# SCH_ART-BadgeV2_0.net
KiCad netlist of a schematic drawn in EasyEDA
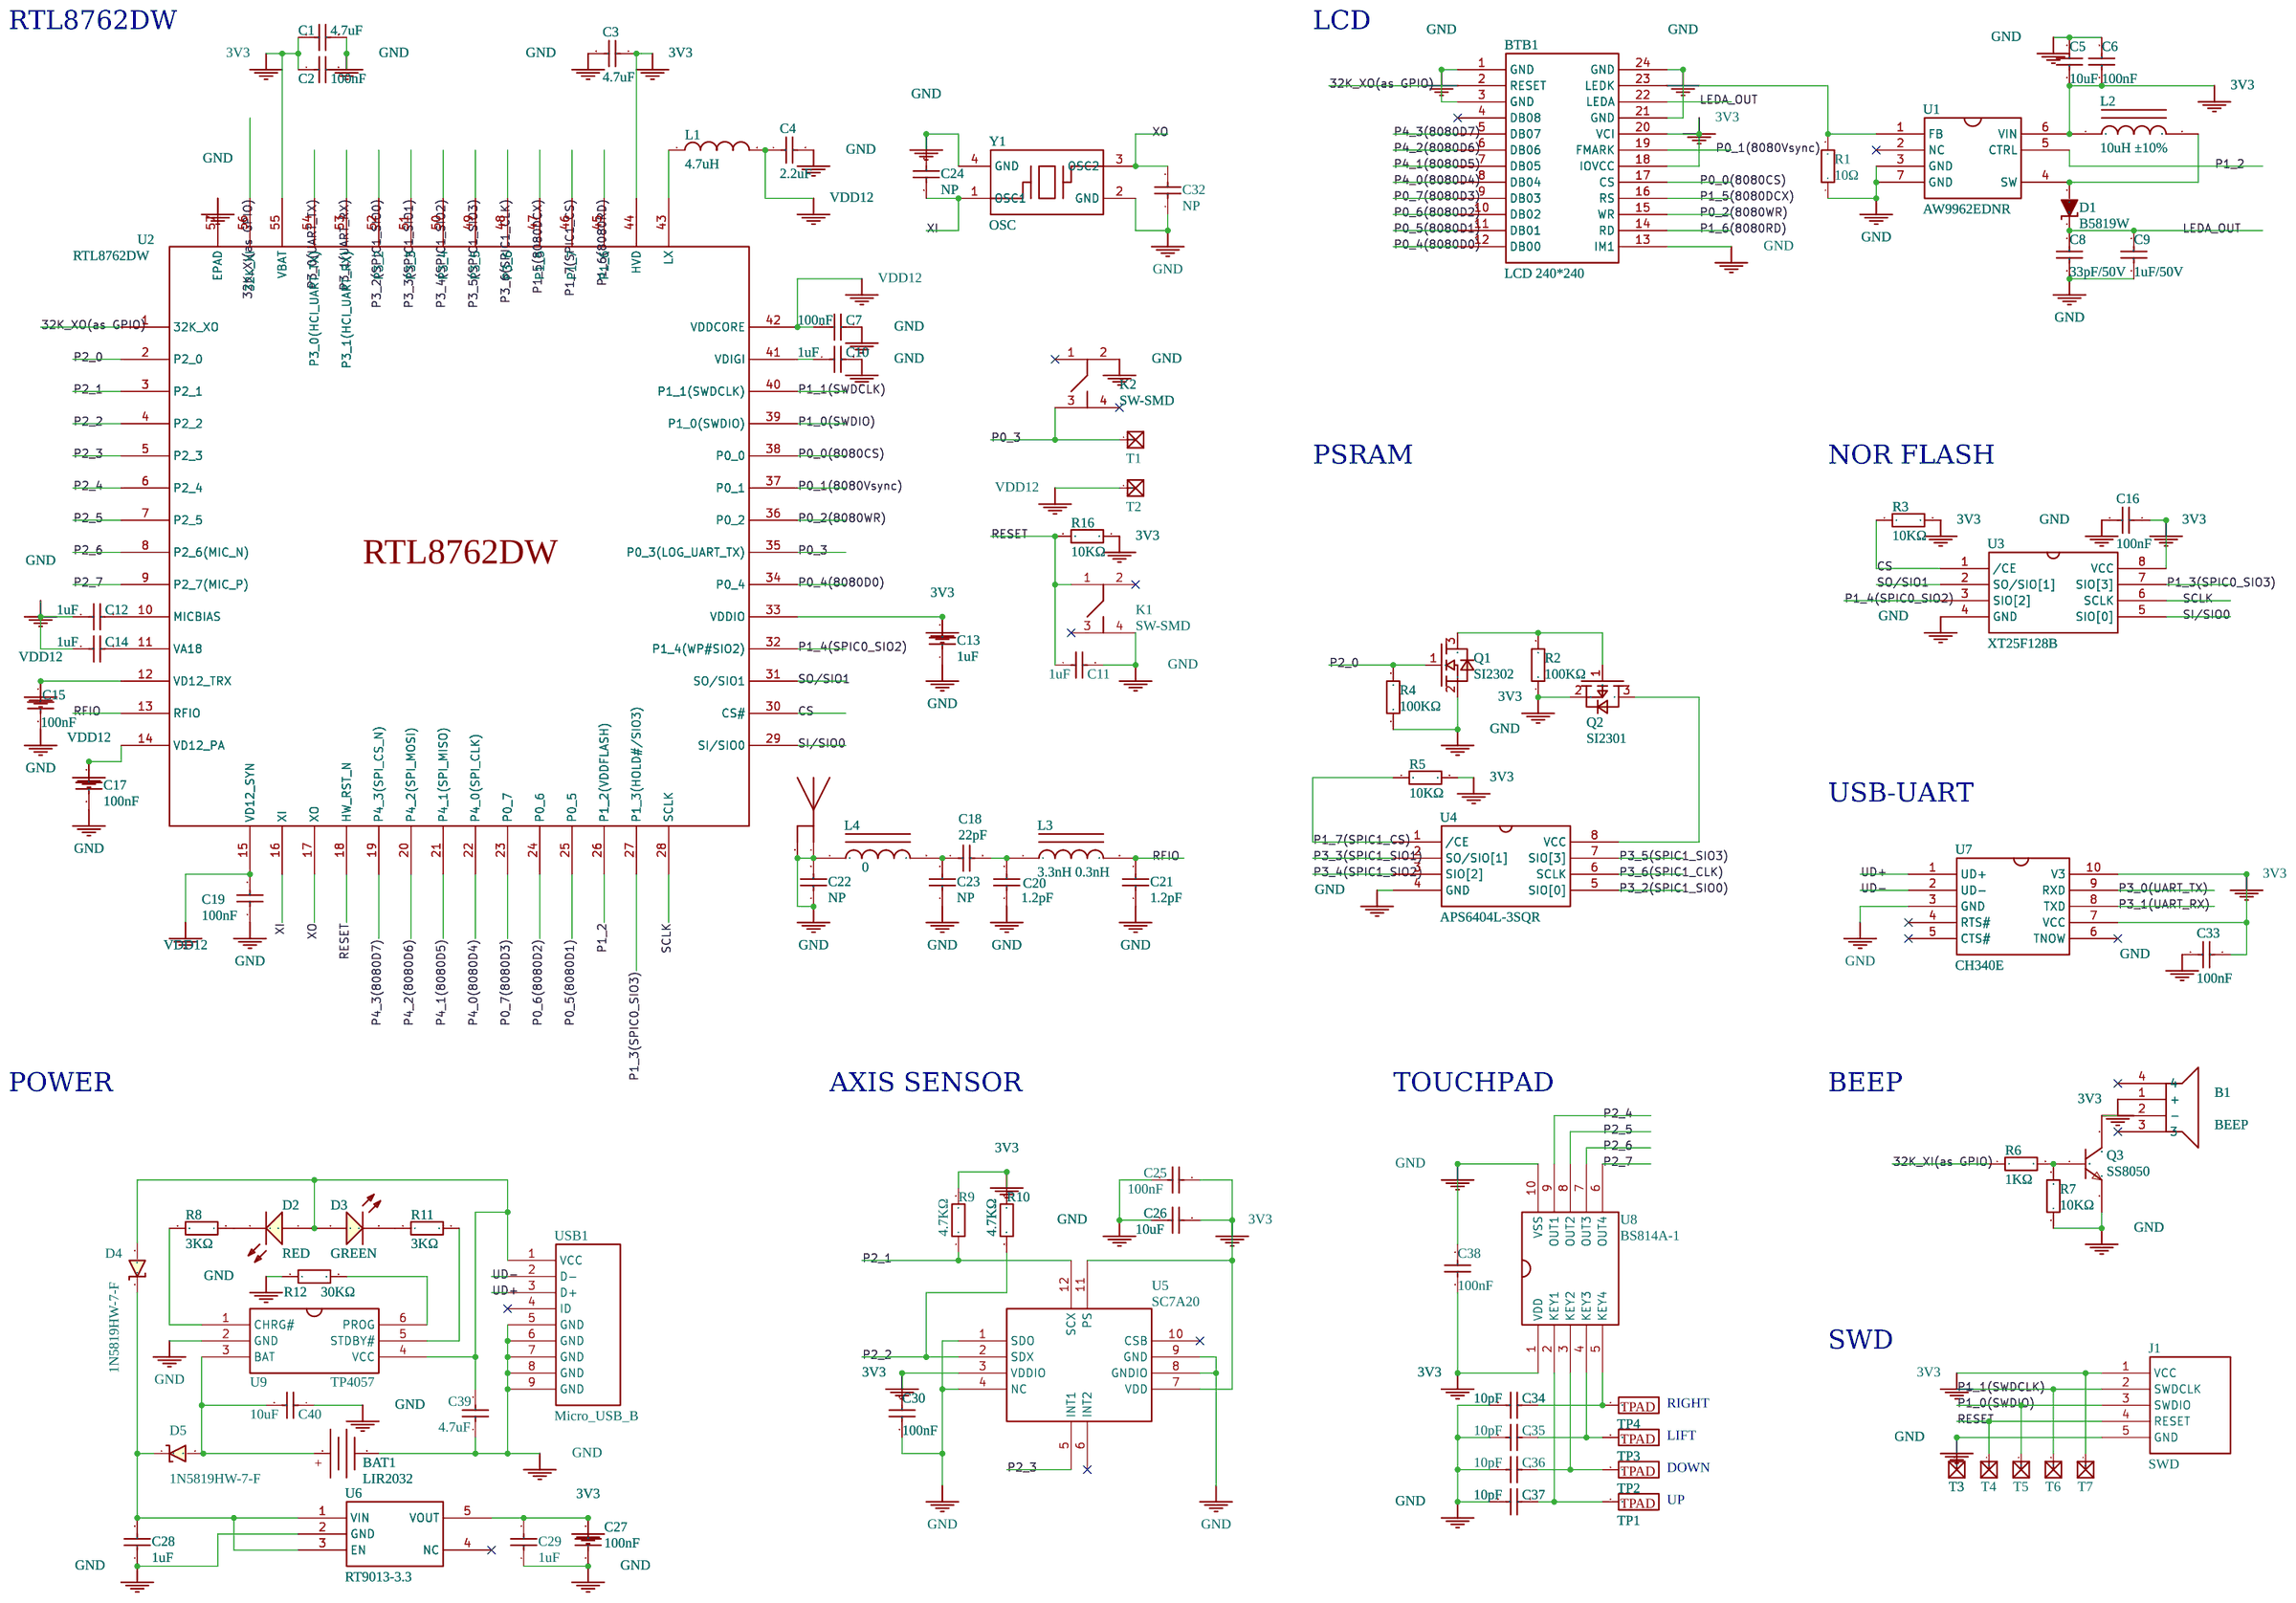
[diagram p0: schematic sheet]

(export (version "E")
  (design (tool "Eeschema 10.0.6"))
  (components
    (comp (ref "*") (value "antenna") (libsource (lib "") (part "Unknown_570_-570")))
    (comp (ref "B1") (value "BEEP") (libsource (lib "") (part "Unknown_1430_-340")))
    (comp (ref "BAT1") (value "LIR2032") (libsource (lib "") (part "Unknown_270_-150")))
    (comp (ref "BTB1") (value "LCD 240*240") (libsource (lib "") (part "Unknown_1000_-1020")))
    (comp (ref "C1") (value "4.7uF") (libsource (lib "") (part "Unknown_230_-1030")))
    (comp (ref "C2") (value "100nF") (libsource (lib "") (part "Unknown_230_-1010")))
    (comp (ref "C3") (value "4.7uF") (libsource (lib "") (part "Unknown_480_-1020")))
    (comp (ref "C4") (value "2.2uF") (libsource (lib "") (part "Unknown_520_-960")))
    (comp (ref "C5") (value "10uF") (libsource (lib "") (part "Unknown_1350_-980")))
    (comp (ref "C6") (value "100nF") (libsource (lib "") (part "Unknown_1370_-980")))
    (comp (ref "C7") (value "100nF") (libsource (lib "") (part "Unknown_620_-850")))
    (comp (ref "C8") (value "33pF/50V") (libsource (lib "") (part "Unknown_1350_-860")))
    (comp (ref "C9") (value "1uF/50V") (libsource (lib "") (part "Unknown_1390_-860")))
    (comp (ref "C10") (value "1uF") (libsource (lib "") (part "Unknown_550_-830")))
    (comp (ref "C11") (value "1uF") (libsource (lib "") (part "Unknown_700_-640")))
    (comp (ref "C12") (value "1uF") (libsource (lib "") (part "Unknown_90_-670")))
    (comp (ref "C13") (value "1uF") (libsource (lib "") (part "Unknown_650_-620")))
    (comp (ref "C14") (value "1uF") (libsource (lib "") (part "Unknown_90_-650")))
    (comp (ref "C15") (value "100nF") (libsource (lib "") (part "Unknown_90_-650_1")))
    (comp (ref "C16") (value "100nF") (libsource (lib "") (part "Unknown_1350_-730")))
    (comp (ref "C17") (value "100nF") (libsource (lib "") (part "Unknown_120_-600")))
    (comp (ref "C18") (value "22pF") (libsource (lib "") (part "Unknown_630_-520")))
    (comp (ref "C19") (value "100nF") (libsource (lib "") (part "Unknown_220_-460")))
    (comp (ref "C20") (value "1.2pF") (libsource (lib "") (part "Unknown_690_-470")))
    (comp (ref "C21") (value "1.2pF") (libsource (lib "") (part "Unknown_770_-470")))
    (comp (ref "C22") (value "NP") (libsource (lib "") (part "Unknown_570_-470")))
    (comp (ref "C23") (value "NP") (libsource (lib "") (part "Unknown_650_-470")))
    (comp (ref "C24") (value "NP") (libsource (lib "") (part "Unknown_640_-910")))
    (comp (ref "C25") (value "100nF") (libsource (lib "") (part "Unknown_830_-320")))
    (comp (ref "C26") (value "10uF") (libsource (lib "") (part "Unknown_760_-295")))
    (comp (ref "C27") (value "100nF") (libsource (lib "") (part "Unknown_430_-60")))
    (comp (ref "C28") (value "1uF") (libsource (lib "") (part "Unknown_150_-60")))
    (comp (ref "C29") (value "1uF") (libsource (lib "") (part "Unknown_390_-60")))
    (comp (ref "C30") (value "100nF") (libsource (lib "") (part "Unknown_625_-140")))
    (comp (ref "C32") (value "NP") (libsource (lib "") (part "Unknown_790_-900")))
    (comp (ref "C33") (value "100nF") (libsource (lib "") (part "Unknown_1470_-460")))
    (comp (ref "C34") (value "10pF") (libsource (lib "") (part "Unknown_1040_-180")))
    (comp (ref "C35") (value "10pF") (libsource (lib "") (part "Unknown_1040_-160")))
    (comp (ref "C36") (value "10pF") (libsource (lib "") (part "Unknown_1040_-140")))
    (comp (ref "C37") (value "10pF") (libsource (lib "") (part "Unknown_1040_-120")))
    (comp (ref "C38") (value "100nF") (libsource (lib "") (part "Unknown_970_-230")))
    (comp (ref "C39") (value "4.7uF") (libsource (lib "") (part "Unknown_360_-140")))
    (comp (ref "C40") (value "10uF") (libsource (lib "") (part "Unknown_280_-180")))
    (comp (ref "D1") (value "B5819W") (libsource (lib "") (part "Unknown_1355_-929")))
    (comp (ref "D2") (value "RED") (libsource (lib "") (part "Unknown_290_-280")))
    (comp (ref "D3") (value "GREEN") (libsource (lib "") (part "Unknown_230_-300")))
    (comp (ref "D4") (value "1N5819HW-7-F") (libsource (lib "") (part "Unknown_155_-270")))
    (comp (ref "D5") (value "1N5819HW-7-F") (libsource (lib "") (part "Unknown_180_-145")))
    (comp (ref "J1") (value "SWD") (libsource (lib "") (part "Unknown_1400_-210")))
    (comp (ref "K1") (value "SW-SMD") (libsource (lib "") (part "Unknown_750_-690")))
    (comp (ref "K2") (value "SW-SMD") (libsource (lib "") (part "Unknown_740_-830")))
    (comp (ref "L1") (value "4.7uH") (libsource (lib "") (part "Unknown_490_-960")))
    (comp (ref "L2") (value "10uH ±10%") (libsource (lib "") (part "Unknown_1330_-970")))
    (comp (ref "L3") (value "3.3nH 0.3nH") (libsource (lib "") (part "Unknown_670_-520")))
    (comp (ref "L4") (value "0") (libsource (lib "") (part "Unknown_550_-520")))
    (comp (ref "Q1") (value "SI2302") (libsource (lib "") (part "Unknown_960_-640")))
    (comp (ref "Q2") (value "SI2301") (libsource (lib "") (part "Unknown_1060_-630")))
    (comp (ref "Q3") (value "SS8050") (libsource (lib "") (part "Unknown_1310_-340")))
    (comp (ref "R1") (value "10Ω") (libsource (lib "") (part "Unknown_1200_-950")))
    (comp (ref "R2") (value "100KΩ") (libsource (lib "") (part "Unknown_1020_-640")))
    (comp (ref "R3") (value "10KΩ") (libsource (lib "") (part "Unknown_1250_-730")))
    (comp (ref "R4") (value "100KΩ") (libsource (lib "") (part "Unknown_930_-620")))
    (comp (ref "R5") (value "10KΩ") (libsource (lib "") (part "Unknown_950_-570")))
    (comp (ref "R6") (value "1KΩ") (libsource (lib "") (part "Unknown_1320_-330")))
    (comp (ref "R7") (value "10KΩ") (libsource (lib "") (part "Unknown_1340_-310")))
    (comp (ref "R8") (value "3KΩ") (libsource (lib "") (part "Unknown_190_-290")))
    (comp (ref "R9") (value "4.7KΩ") (libsource (lib "") (part "Unknown_660_-295")))
    (comp (ref "R10") (value "4.7KΩ") (libsource (lib "") (part "Unknown_690_-295")))
    (comp (ref "R11") (value "3KΩ") (libsource (lib "") (part "Unknown_330_-290")))
    (comp (ref "R12") (value "30KΩ") (libsource (lib "") (part "Unknown_260_-260")))
    (comp (ref "R16") (value "10KΩ") (libsource (lib "") (part "Unknown_740_-720")))
    (comp (ref "T1") (value "TEST POINT") (libsource (lib "") (part "Unknown_760_-780")))
    (comp (ref "T2") (value "TEST POINT") (libsource (lib "") (part "Unknown_760_-750")))
    (comp (ref "T3") (value "TEST POINT") (libsource (lib "") (part "Unknown_1280_-150")))
    (comp (ref "T4") (value "TEST POINT") (libsource (lib "") (part "Unknown_1300_-150")))
    (comp (ref "T5") (value "TEST POINT") (libsource (lib "") (part "Unknown_1320_-150")))
    (comp (ref "T6") (value "TEST POINT") (libsource (lib "") (part "Unknown_1340_-150")))
    (comp (ref "T7") (value "TEST POINT") (libsource (lib "") (part "Unknown_1360_-150")))
    (comp (ref "TP1") (value "TPAD") (libsource (lib "") (part "Unknown_1070_-120")))
    (comp (ref "TP2") (value "TPAD") (libsource (lib "") (part "Unknown_1070_-140")))
    (comp (ref "TP3") (value "TPAD") (libsource (lib "") (part "Unknown_1070_-160")))
    (comp (ref "TP4") (value "TPAD") (libsource (lib "") (part "Unknown_1070_-180")))
    (comp (ref "U1") (value "AW9962EDNR") (libsource (lib "") (part "Unknown_1260_-980")))
    (comp (ref "U2") (value "RTL8762DW") (libsource (lib "") (part "Unknown_170_-900")))
    (comp (ref "U3") (value "XT25F128B") (libsource (lib "") (part "Unknown_1300_-710")))
    (comp (ref "U4") (value "APS6404L-3SQR") (libsource (lib "") (part "Unknown_960_-540")))
    (comp (ref "U5") (value "SC7A20") (libsource (lib "") (part "Unknown_690_-240")))
    (comp (ref "U6") (value "RT9013-3.3") (libsource (lib "") (part "Unknown_280_-120")))
    (comp (ref "U7") (value "CH340E") (libsource (lib "") (part "Unknown_1280_-520")))
    (comp (ref "U8") (value "BS814A-1") (libsource (lib "") (part "Unknown_1010_-230")))
    (comp (ref "U9") (value "TP4057") (libsource (lib "") (part "Unknown_220_-240")))
    (comp (ref "USB1") (value "Micro_USB_B") (libsource (lib "") (part "Unknown_410_-280")))
    (comp (ref "Y1") (value "OSC") (libsource (lib "") (part "Unknown_690_-960")))
  )
  (nets
    (net (code "1") (name "/32K_XI(as GPIO)") (class "Default")
      (node (ref "R6") (pin "1") (pinfunction "1_1") (pintype "unspecified"))
      (node (ref "U2") (pin "56") (pinfunction "32K_XI_56") (pintype "unspecified"))
    )
    (net (code "2") (name "/32K_XO(as GPIO)") (class "Default")
      (node (ref "BTB1") (pin "2") (pinfunction "RESET_2") (pintype "unspecified"))
      (node (ref "U2") (pin "1") (pinfunction "32K_XO_1") (pintype "unspecified"))
    )
    (net (code "3") (name "/CS") (class "Default")
      (node (ref "R3") (pin "1") (pinfunction "1_1") (pintype "unspecified"))
      (node (ref "U2") (pin "30") (pinfunction "CS#_30") (pintype "unspecified"))
      (node (ref "U3") (pin "1") (pinfunction "/CE_1") (pintype "unspecified"))
    )
    (net (code "4") (name "/LEDA_OUT") (class "Default")
      (node (ref "BTB1") (pin "22") (pinfunction "LEDA_22") (pintype "unspecified"))
      (node (ref "C8") (pin "2") (pinfunction "2_2") (pintype "unspecified"))
      (node (ref "C9") (pin "2") (pinfunction "2_2") (pintype "unspecified"))
      (node (ref "D1") (pin "1") (pinfunction "1_1") (pintype "unspecified"))
    )
    (net (code "5") (name "/P0_0(8080CS)") (class "Default")
      (node (ref "BTB1") (pin "17") (pinfunction "CS_17") (pintype "unspecified"))
      (node (ref "U2") (pin "38") (pinfunction "P0_0_38") (pintype "unspecified"))
    )
    (net (code "6") (name "/P0_1(8080Vsync)") (class "Default")
      (node (ref "BTB1") (pin "19") (pinfunction "FMARK_19") (pintype "unspecified"))
      (node (ref "U2") (pin "37") (pinfunction "P0_1_37") (pintype "unspecified"))
    )
    (net (code "7") (name "/P0_2(8080WR)") (class "Default")
      (node (ref "BTB1") (pin "15") (pinfunction "WR_15") (pintype "unspecified"))
      (node (ref "U2") (pin "36") (pinfunction "P0_2_36") (pintype "unspecified"))
    )
    (net (code "8") (name "/P0_3") (class "Default")
      (node (ref "K2") (pin "3") (pintype "unspecified"))
      (node (ref "T1") (pin "1") (pinfunction "TP_1") (pintype "unspecified"))
      (node (ref "U2") (pin "35") (pinfunction "P0_3(LOG_UART_TX)_35") (pintype "unspecified"))
    )
    (net (code "9") (name "/P0_4(8080D0)") (class "Default")
      (node (ref "BTB1") (pin "12") (pinfunction "DB00_12") (pintype "unspecified"))
      (node (ref "U2") (pin "34") (pinfunction "P0_4_34") (pintype "unspecified"))
    )
    (net (code "10") (name "/P0_5(8080D1)") (class "Default")
      (node (ref "BTB1") (pin "11") (pinfunction "DB01_11") (pintype "unspecified"))
      (node (ref "U2") (pin "25") (pinfunction "P0_5_25") (pintype "unspecified"))
    )
    (net (code "11") (name "/P0_6(8080D2)") (class "Default")
      (node (ref "BTB1") (pin "10") (pinfunction "DB02_10") (pintype "unspecified"))
      (node (ref "U2") (pin "24") (pinfunction "P0_6_24") (pintype "unspecified"))
    )
    (net (code "12") (name "/P0_7(8080D3)") (class "Default")
      (node (ref "BTB1") (pin "9") (pinfunction "DB03_9") (pintype "unspecified"))
      (node (ref "U2") (pin "23") (pinfunction "P0_7_23") (pintype "unspecified"))
    )
    (net (code "13") (name "/P1_0(SWDIO)") (class "Default")
      (node (ref "J1") (pin "3") (pinfunction "SWDIO_3") (pintype "unspecified"))
      (node (ref "T5") (pin "1") (pinfunction "TP_1") (pintype "unspecified"))
      (node (ref "U2") (pin "39") (pinfunction "P1_0(SWDIO)_39") (pintype "unspecified"))
    )
    (net (code "14") (name "/P1_1(SWDCLK)") (class "Default")
      (node (ref "J1") (pin "2") (pinfunction "SWDCLK_2") (pintype "unspecified"))
      (node (ref "T6") (pin "1") (pinfunction "TP_1") (pintype "unspecified"))
      (node (ref "U2") (pin "40") (pinfunction "P1_1(SWDCLK)_40") (pintype "unspecified"))
    )
    (net (code "15") (name "/P1_2") (class "Default")
      (node (ref "U1") (pin "5") (pinfunction "CTRL_5") (pintype "unspecified"))
      (node (ref "U2") (pin "26") (pinfunction "P1_2(VDDFLASH)_26") (pintype "unspecified"))
    )
    (net (code "16") (name "/P1_3(SPIC0_SIO3)") (class "Default")
      (node (ref "U2") (pin "27") (pinfunction "P1_3(HOLD#/SIO3)_27") (pintype "unspecified"))
      (node (ref "U3") (pin "7") (pinfunction "SIO[3]_7") (pintype "unspecified"))
    )
    (net (code "17") (name "/P1_4(SPIC0_SIO2)") (class "Default")
      (node (ref "U2") (pin "32") (pinfunction "P1_4(WP#SIO2)_32") (pintype "unspecified"))
      (node (ref "U3") (pin "3") (pinfunction "SIO[2]_3") (pintype "unspecified"))
    )
    (net (code "18") (name "/P1_5(8080DCX)") (class "Default")
      (node (ref "BTB1") (pin "16") (pinfunction "RS_16") (pintype "unspecified"))
      (node (ref "U2") (pin "47") (pinfunction "P1_5_47") (pintype "unspecified"))
    )
    (net (code "19") (name "/P1_6(8080RD)") (class "Default")
      (node (ref "BTB1") (pin "14") (pinfunction "RD_14") (pintype "unspecified"))
      (node (ref "U2") (pin "45") (pinfunction "P1_6_45") (pintype "unspecified"))
    )
    (net (code "20") (name "/P1_7(SPIC1_CS)") (class "Default")
      (node (ref "R5") (pin "1") (pinfunction "1_1") (pintype "unspecified"))
      (node (ref "U2") (pin "46") (pinfunction "P1_7_46") (pintype "unspecified"))
      (node (ref "U4") (pin "1") (pinfunction "/CE_1") (pintype "unspecified"))
    )
    (net (code "21") (name "/P2_0") (class "Default")
      (node (ref "Q1") (pin "1") (pinfunction "1_1") (pintype "unspecified"))
      (node (ref "R4") (pin "2") (pinfunction "2_2") (pintype "unspecified"))
      (node (ref "U2") (pin "2") (pinfunction "P2_0_2") (pintype "unspecified"))
    )
    (net (code "22") (name "/P2_1") (class "Default")
      (node (ref "R9") (pin "1") (pinfunction "1_1") (pintype "unspecified"))
      (node (ref "U2") (pin "3") (pinfunction "P2_1_3") (pintype "unspecified"))
      (node (ref "U5") (pin "12") (pinfunction "SCX_12") (pintype "unspecified"))
    )
    (net (code "23") (name "/P2_2") (class "Default")
      (node (ref "R10") (pin "1") (pinfunction "1_1") (pintype "unspecified"))
      (node (ref "U2") (pin "4") (pinfunction "P2_2_4") (pintype "unspecified"))
      (node (ref "U5") (pin "2") (pinfunction "SDX_2") (pintype "unspecified"))
    )
    (net (code "24") (name "/P2_3") (class "Default")
      (node (ref "U2") (pin "5") (pinfunction "P2_3_5") (pintype "unspecified"))
      (node (ref "U5") (pin "5") (pinfunction "INT1_5") (pintype "unspecified"))
    )
    (net (code "25") (name "/P2_4") (class "Default")
      (node (ref "U2") (pin "6") (pinfunction "P2_4_6") (pintype "unspecified"))
      (node (ref "U8") (pin "9") (pinfunction "OUT1_9") (pintype "unspecified"))
    )
    (net (code "26") (name "/P2_5") (class "Default")
      (node (ref "U2") (pin "7") (pinfunction "P2_5_7") (pintype "unspecified"))
      (node (ref "U8") (pin "8") (pinfunction "OUT2_8") (pintype "unspecified"))
    )
    (net (code "27") (name "/P2_6") (class "Default")
      (node (ref "U2") (pin "8") (pinfunction "P2_6(MIC_N)_8") (pintype "unspecified"))
      (node (ref "U8") (pin "7") (pinfunction "OUT3_7") (pintype "unspecified"))
    )
    (net (code "28") (name "/P2_7") (class "Default")
      (node (ref "U2") (pin "9") (pinfunction "P2_7(MIC_P)_9") (pintype "unspecified"))
      (node (ref "U8") (pin "6") (pinfunction "OUT4_6") (pintype "unspecified"))
    )
    (net (code "29") (name "/P3_0(UART_TX)") (class "Default")
      (node (ref "U2") (pin "54") (pinfunction "P3_0(HCI_UART_TX)_54") (pintype "unspecified"))
      (node (ref "U7") (pin "9") (pinfunction "RXD_9") (pintype "unspecified"))
    )
    (net (code "30") (name "/P3_1(UART_RX)") (class "Default")
      (node (ref "U2") (pin "53") (pinfunction "P3_1(HCI_UART_RX)_53") (pintype "unspecified"))
      (node (ref "U7") (pin "8") (pinfunction "TXD_8") (pintype "unspecified"))
    )
    (net (code "31") (name "/P3_2(SPIC1_SIO0)") (class "Default")
      (node (ref "U2") (pin "52") (pinfunction "P3_2_52") (pintype "unspecified"))
      (node (ref "U4") (pin "5") (pinfunction "SIO[0]_5") (pintype "unspecified"))
    )
    (net (code "32") (name "/P3_3(SPIC1_SIO1)") (class "Default")
      (node (ref "U2") (pin "51") (pinfunction "P3_3_51") (pintype "unspecified"))
      (node (ref "U4") (pin "2") (pinfunction "SO/SIO[1]_2") (pintype "unspecified"))
    )
    (net (code "33") (name "/P3_4(SPIC1_SIO2)") (class "Default")
      (node (ref "U2") (pin "50") (pinfunction "P3_4_50") (pintype "unspecified"))
      (node (ref "U4") (pin "3") (pinfunction "SIO[2]_3") (pintype "unspecified"))
    )
    (net (code "34") (name "/P3_5(SPIC1_SIO3)") (class "Default")
      (node (ref "U2") (pin "49") (pinfunction "P3_5_49") (pintype "unspecified"))
      (node (ref "U4") (pin "7") (pinfunction "SIO[3]_7") (pintype "unspecified"))
    )
    (net (code "35") (name "/P3_6(SPIC1_CLK)") (class "Default")
      (node (ref "U2") (pin "48") (pinfunction "P3_6_48") (pintype "unspecified"))
      (node (ref "U4") (pin "6") (pinfunction "SCLK_6") (pintype "unspecified"))
    )
    (net (code "36") (name "/P4_0(8080D4)") (class "Default")
      (node (ref "BTB1") (pin "8") (pinfunction "DB04_8") (pintype "unspecified"))
      (node (ref "U2") (pin "22") (pinfunction "P4_0(SPI_CLK)_22") (pintype "unspecified"))
    )
    (net (code "37") (name "/P4_1(8080D5)") (class "Default")
      (node (ref "BTB1") (pin "7") (pinfunction "DB05_7") (pintype "unspecified"))
      (node (ref "U2") (pin "21") (pinfunction "P4_1(SPI_MISO)_21") (pintype "unspecified"))
    )
    (net (code "38") (name "/P4_2(8080D6)") (class "Default")
      (node (ref "BTB1") (pin "6") (pinfunction "DB06_6") (pintype "unspecified"))
      (node (ref "U2") (pin "20") (pinfunction "P4_2(SPI_MOSI)_20") (pintype "unspecified"))
    )
    (net (code "39") (name "/P4_3(8080D7)") (class "Default")
      (node (ref "BTB1") (pin "5") (pinfunction "DB07_5") (pintype "unspecified"))
      (node (ref "U2") (pin "19") (pinfunction "P4_3(SPI_CS_N)_19") (pintype "unspecified"))
    )
    (net (code "40") (name "/RESET") (class "Default")
      (node (ref "C11") (pin "1") (pinfunction "1_1") (pintype "unspecified"))
      (node (ref "J1") (pin "4") (pinfunction "RESET_4") (pintype "unspecified"))
      (node (ref "K1") (pin "1") (pintype "unspecified"))
      (node (ref "R16") (pin "2") (pinfunction "2_2") (pintype "unspecified"))
      (node (ref "T4") (pin "1") (pinfunction "TP_1") (pintype "unspecified"))
      (node (ref "U2") (pin "18") (pinfunction "HW_RST_N_18") (pintype "unspecified"))
    )
    (net (code "41") (name "/RFIO") (class "Default")
      (node (ref "C21") (pin "2") (pinfunction "2_2") (pintype "unspecified"))
      (node (ref "L3") (pin "2") (pinfunction "2_2") (pintype "unspecified"))
      (node (ref "U2") (pin "13") (pinfunction "RFIO_13") (pintype "unspecified"))
    )
    (net (code "42") (name "/SCLK") (class "Default")
      (node (ref "U2") (pin "28") (pinfunction "SCLK_28") (pintype "unspecified"))
      (node (ref "U3") (pin "6") (pinfunction "SCLK_6") (pintype "unspecified"))
    )
    (net (code "43") (name "/SI{slash}SIO0") (class "Default")
      (node (ref "U2") (pin "29") (pinfunction "SI/SIO0_29") (pintype "unspecified"))
      (node (ref "U3") (pin "5") (pinfunction "SIO[0]_5") (pintype "unspecified"))
    )
    (net (code "44") (name "/SO{slash}SIO1") (class "Default")
      (node (ref "U2") (pin "31") (pinfunction "SO/SIO1_31") (pintype "unspecified"))
      (node (ref "U3") (pin "2") (pinfunction "SO/SIO[1]_2") (pintype "unspecified"))
    )
    (net (code "45") (name "/UD+") (class "Default")
      (node (ref "U7") (pin "1") (pinfunction "UD+_1") (pintype "unspecified"))
      (node (ref "USB1") (pin "3") (pinfunction "D+_3") (pintype "unspecified"))
    )
    (net (code "46") (name "/UD-") (class "Default")
      (node (ref "U7") (pin "2") (pinfunction "UD-_2") (pintype "unspecified"))
      (node (ref "USB1") (pin "2") (pinfunction "D-_2") (pintype "unspecified"))
    )
    (net (code "47") (name "/XI") (class "Default")
      (node (ref "C24") (pin "1") (pinfunction "1_1") (pintype "unspecified"))
      (node (ref "U2") (pin "16") (pinfunction "XI_16") (pintype "unspecified"))
      (node (ref "Y1") (pin "1") (pinfunction "OSC1_1") (pintype "unspecified"))
    )
    (net (code "48") (name "/XO") (class "Default")
      (node (ref "C32") (pin "2") (pinfunction "2_2") (pintype "unspecified"))
      (node (ref "U2") (pin "17") (pinfunction "XO_17") (pintype "unspecified"))
      (node (ref "Y1") (pin "3") (pinfunction "OSC2_3") (pintype "unspecified"))
    )
    (net (code "49") (name "3V3") (class "Default")
      (node (ref "B1") (pin "1") (pinfunction "+_1") (pintype "unspecified"))
      (node (ref "BTB1") (pin "18") (pinfunction "IOVCC_18") (pintype "unspecified"))
      (node (ref "BTB1") (pin "20") (pinfunction "VCI_20") (pintype "unspecified"))
      (node (ref "C1") (pin "1") (pinfunction "1_1") (pintype "unspecified"))
      (node (ref "C13") (pin "2") (pinfunction "2_2") (pintype "unspecified"))
      (node (ref "C16") (pin "2") (pinfunction "2_2") (pintype "unspecified"))
      (node (ref "C2") (pin "1") (pinfunction "1_1") (pintype "unspecified"))
      (node (ref "C25") (pin "1") (pinfunction "1_1") (pintype "unspecified"))
      (node (ref "C26") (pin "2") (pinfunction "2_2") (pintype "unspecified"))
      (node (ref "C27") (pin "2") (pinfunction "2_2") (pintype "unspecified"))
      (node (ref "C29") (pin "2") (pinfunction "2_2") (pintype "unspecified"))
      (node (ref "C3") (pin "1") (pinfunction "1_1") (pintype "unspecified"))
      (node (ref "C30") (pin "2") (pinfunction "2_2") (pintype "unspecified"))
      (node (ref "C33") (pin "1") (pinfunction "1_1") (pintype "unspecified"))
      (node (ref "C38") (pin "1") (pinfunction "1_1") (pintype "unspecified"))
      (node (ref "C5") (pin "1") (pinfunction "1_1") (pintype "unspecified"))
      (node (ref "C6") (pin "1") (pinfunction "1_1") (pintype "unspecified"))
      (node (ref "J1") (pin "1") (pinfunction "VCC_1") (pintype "unspecified"))
      (node (ref "L2") (pin "1") (pinfunction "1_1") (pintype "unspecified"))
      (node (ref "Q2") (pin "2") (pinfunction "2_2") (pintype "unspecified"))
      (node (ref "R10") (pin "2") (pinfunction "2_2") (pintype "unspecified"))
      (node (ref "R16") (pin "1") (pinfunction "1_1") (pintype "unspecified"))
      (node (ref "R2") (pin "1") (pinfunction "1_1") (pintype "unspecified"))
      (node (ref "R3") (pin "2") (pinfunction "2_2") (pintype "unspecified"))
      (node (ref "R5") (pin "2") (pinfunction "2_2") (pintype "unspecified"))
      (node (ref "R9") (pin "2") (pinfunction "2_2") (pintype "unspecified"))
      (node (ref "T7") (pin "1") (pinfunction "TP_1") (pintype "unspecified"))
      (node (ref "U1") (pin "6") (pinfunction "VIN_6") (pintype "unspecified"))
      (node (ref "U2") (pin "33") (pinfunction "VDDIO_33") (pintype "unspecified"))
      (node (ref "U2") (pin "44") (pinfunction "HVD_44") (pintype "unspecified"))
      (node (ref "U2") (pin "55") (pinfunction "VBAT_55") (pintype "unspecified"))
      (node (ref "U3") (pin "8") (pinfunction "VCC_8") (pintype "unspecified"))
      (node (ref "U5") (pin "11") (pinfunction "PS_11") (pintype "unspecified"))
      (node (ref "U5") (pin "3") (pinfunction "VDDIO_3") (pintype "unspecified"))
      (node (ref "U5") (pin "7") (pinfunction "VDD_7") (pintype "unspecified"))
      (node (ref "U6") (pin "5") (pinfunction "VOUT_5") (pintype "unspecified"))
      (node (ref "U7") (pin "10") (pinfunction "V3_10") (pintype "unspecified"))
      (node (ref "U7") (pin "7") (pinfunction "VCC_7") (pintype "unspecified"))
      (node (ref "U8") (pin "1") (pinfunction "VDD_1") (pintype "unspecified"))
    )
    (net (code "50") (name "GND") (class "Default")
      (node (ref "*") (pin "1") (pintype "unspecified"))
      (node (ref "*") (pin "2") (pintype "unspecified"))
      (node (ref "BAT1") (pin "2") (pintype "unspecified"))
      (node (ref "BTB1") (pin "1") (pinfunction "GND_1") (pintype "unspecified"))
      (node (ref "BTB1") (pin "13") (pinfunction "IM1_13") (pintype "unspecified"))
      (node (ref "BTB1") (pin "21") (pinfunction "GND_21") (pintype "unspecified"))
      (node (ref "BTB1") (pin "24") (pinfunction "GND_24") (pintype "unspecified"))
      (node (ref "BTB1") (pin "3") (pinfunction "GND_3") (pintype "unspecified"))
      (node (ref "C1") (pin "2") (pinfunction "2_2") (pintype "unspecified"))
      (node (ref "C10") (pin "2") (pinfunction "2_2") (pintype "unspecified"))
      (node (ref "C11") (pin "2") (pinfunction "2_2") (pintype "unspecified"))
      (node (ref "C12") (pin "1") (pinfunction "1_1") (pintype "unspecified"))
      (node (ref "C13") (pin "1") (pinfunction "1_1") (pintype "unspecified"))
      (node (ref "C14") (pin "1") (pinfunction "1_1") (pintype "unspecified"))
      (node (ref "C15") (pin "2") (pinfunction "2_2") (pintype "unspecified"))
      (node (ref "C16") (pin "1") (pinfunction "1_1") (pintype "unspecified"))
      (node (ref "C17") (pin "2") (pinfunction "2_2") (pintype "unspecified"))
      (node (ref "C19") (pin "1") (pinfunction "1_1") (pintype "unspecified"))
      (node (ref "C2") (pin "2") (pinfunction "2_2") (pintype "unspecified"))
      (node (ref "C20") (pin "1") (pinfunction "1_1") (pintype "unspecified"))
      (node (ref "C21") (pin "1") (pinfunction "1_1") (pintype "unspecified"))
      (node (ref "C22") (pin "1") (pinfunction "1_1") (pintype "unspecified"))
      (node (ref "C22") (pin "2") (pinfunction "2_2") (pintype "unspecified"))
      (node (ref "C23") (pin "1") (pinfunction "1_1") (pintype "unspecified"))
      (node (ref "C24") (pin "2") (pinfunction "2_2") (pintype "unspecified"))
      (node (ref "C25") (pin "2") (pinfunction "2_2") (pintype "unspecified"))
      (node (ref "C26") (pin "1") (pinfunction "1_1") (pintype "unspecified"))
      (node (ref "C27") (pin "1") (pinfunction "1_1") (pintype "unspecified"))
      (node (ref "C28") (pin "1") (pinfunction "1_1") (pintype "unspecified"))
      (node (ref "C29") (pin "1") (pinfunction "1_1") (pintype "unspecified"))
      (node (ref "C3") (pin "2") (pinfunction "2_2") (pintype "unspecified"))
      (node (ref "C30") (pin "1") (pinfunction "1_1") (pintype "unspecified"))
      (node (ref "C32") (pin "1") (pinfunction "1_1") (pintype "unspecified"))
      (node (ref "C33") (pin "2") (pinfunction "2_2") (pintype "unspecified"))
      (node (ref "C34") (pin "2") (pinfunction "2_2") (pintype "unspecified"))
      (node (ref "C35") (pin "2") (pinfunction "2_2") (pintype "unspecified"))
      (node (ref "C36") (pin "2") (pinfunction "2_2") (pintype "unspecified"))
      (node (ref "C37") (pin "2") (pinfunction "2_2") (pintype "unspecified"))
      (node (ref "C38") (pin "2") (pinfunction "2_2") (pintype "unspecified"))
      (node (ref "C39") (pin "1") (pinfunction "1_1") (pintype "unspecified"))
      (node (ref "C4") (pin "2") (pinfunction "2_2") (pintype "unspecified"))
      (node (ref "C40") (pin "1") (pinfunction "1_1") (pintype "unspecified"))
      (node (ref "C5") (pin "2") (pinfunction "2_2") (pintype "unspecified"))
      (node (ref "C6") (pin "2") (pinfunction "2_2") (pintype "unspecified"))
      (node (ref "C7") (pin "1") (pinfunction "1_1") (pintype "unspecified"))
      (node (ref "C8") (pin "1") (pinfunction "1_1") (pintype "unspecified"))
      (node (ref "C9") (pin "1") (pinfunction "1_1") (pintype "unspecified"))
      (node (ref "J1") (pin "5") (pinfunction "GND_5") (pintype "unspecified"))
      (node (ref "K1") (pin "4") (pintype "unspecified"))
      (node (ref "K2") (pin "2") (pintype "unspecified"))
      (node (ref "L4") (pin "1") (pinfunction "1_1") (pintype "unspecified"))
      (node (ref "Q1") (pin "2") (pinfunction "2_2") (pintype "unspecified"))
      (node (ref "Q3") (pin "2") (pinfunction "E_2") (pintype "unspecified"))
      (node (ref "R1") (pin "1") (pinfunction "1_1") (pintype "unspecified"))
      (node (ref "R12") (pin "1") (pinfunction "1_1") (pintype "unspecified"))
      (node (ref "R4") (pin "1") (pinfunction "1_1") (pintype "unspecified"))
      (node (ref "R7") (pin "1") (pinfunction "1_1") (pintype "unspecified"))
      (node (ref "T3") (pin "1") (pinfunction "TP_1") (pintype "unspecified"))
      (node (ref "U1") (pin "3") (pinfunction "GND_3") (pintype "unspecified"))
      (node (ref "U1") (pin "7") (pinfunction "GND_7") (pintype "unspecified"))
      (node (ref "U2") (pin "57") (pinfunction "EPAD_57") (pintype "unspecified"))
      (node (ref "U3") (pin "4") (pinfunction "GND_4") (pintype "unspecified"))
      (node (ref "U4") (pin "4") (pinfunction "GND_4") (pintype "unspecified"))
      (node (ref "U5") (pin "1") (pinfunction "SDO_1") (pintype "unspecified"))
      (node (ref "U5") (pin "4") (pinfunction "NC_4") (pintype "unspecified"))
      (node (ref "U5") (pin "8") (pinfunction "GNDIO_8") (pintype "unspecified"))
      (node (ref "U5") (pin "9") (pinfunction "GND_9") (pintype "unspecified"))
      (node (ref "U6") (pin "2") (pinfunction "GND_2") (pintype "unspecified"))
      (node (ref "U7") (pin "3") (pinfunction "GND_3") (pintype "unspecified"))
      (node (ref "U8") (pin "10") (pinfunction "VSS_10") (pintype "unspecified"))
      (node (ref "U9") (pin "2") (pinfunction "GND_2") (pintype "unspecified"))
      (node (ref "USB1") (pin "5") (pinfunction "GND_5") (pintype "unspecified"))
      (node (ref "USB1") (pin "6") (pinfunction "GND_6") (pintype "unspecified"))
      (node (ref "USB1") (pin "7") (pinfunction "GND_7") (pintype "unspecified"))
      (node (ref "USB1") (pin "8") (pinfunction "GND_8") (pintype "unspecified"))
      (node (ref "USB1") (pin "9") (pinfunction "GND_9") (pintype "unspecified"))
      (node (ref "Y1") (pin "2") (pinfunction "GND_2") (pintype "unspecified"))
      (node (ref "Y1") (pin "4") (pinfunction "GND_4") (pintype "unspecified"))
    )
    (net (code "51") (name "Net-(B1--)") (class "Default")
      (node (ref "B1") (pin "2") (pinfunction "-_2") (pintype "unspecified"))
      (node (ref "Q3") (pin "3") (pinfunction "C_3") (pintype "unspecified"))
    )
    (net (code "52") (name "Net-(BTB1-LEDK)") (class "Default")
      (node (ref "BTB1") (pin "23") (pinfunction "LEDK_23") (pintype "unspecified"))
      (node (ref "R1") (pin "2") (pinfunction "2_2") (pintype "unspecified"))
      (node (ref "U1") (pin "1") (pinfunction "FB_1") (pintype "unspecified"))
    )
    (net (code "53") (name "Net-(C18-Pad1)") (class "Default")
      (node (ref "C18") (pin "1") (pinfunction "1_1") (pintype "unspecified"))
      (node (ref "C23") (pin "2") (pinfunction "2_2") (pintype "unspecified"))
      (node (ref "L4") (pin "2") (pinfunction "2_2") (pintype "unspecified"))
    )
    (net (code "54") (name "Net-(C18-Pad2)") (class "Default")
      (node (ref "C18") (pin "2") (pinfunction "2_2") (pintype "unspecified"))
      (node (ref "C20") (pin "2") (pinfunction "2_2") (pintype "unspecified"))
      (node (ref "L3") (pin "1") (pinfunction "1_1") (pintype "unspecified"))
    )
    (net (code "55") (name "Net-(D2-PadK)") (class "Default")
      (node (ref "D2") (pin "K") (pinfunction "K_K") (pintype "unspecified"))
      (node (ref "R8") (pin "1") (pinfunction "1_1") (pintype "unspecified"))
    )
    (net (code "56") (name "Net-(D3-PadK)") (class "Default")
      (node (ref "D3") (pin "K") (pinfunction "K_K") (pintype "unspecified"))
      (node (ref "R11") (pin "1") (pinfunction "1_1") (pintype "unspecified"))
    )
    (net (code "57") (name "Net-(Q1-Pad3)") (class "Default")
      (node (ref "Q1") (pin "3") (pinfunction "3_3") (pintype "unspecified"))
      (node (ref "Q2") (pin "1") (pinfunction "1_1") (pintype "unspecified"))
      (node (ref "R2") (pin "2") (pinfunction "2_2") (pintype "unspecified"))
    )
    (net (code "58") (name "Net-(Q3-B)") (class "Default")
      (node (ref "Q3") (pin "1") (pinfunction "B_1") (pintype "unspecified"))
      (node (ref "R6") (pin "2") (pinfunction "2_2") (pintype "unspecified"))
      (node (ref "R7") (pin "2") (pinfunction "2_2") (pintype "unspecified"))
    )
    (net (code "59") (name "Net-(U1-SW)") (class "Default")
      (node (ref "D1") (pin "2") (pinfunction "2_2") (pintype "unspecified"))
      (node (ref "L2") (pin "2") (pinfunction "2_2") (pintype "unspecified"))
      (node (ref "U1") (pin "4") (pinfunction "SW_4") (pintype "unspecified"))
    )
    (net (code "60") (name "Net-(U2-LX)") (class "Default")
      (node (ref "L1") (pin "1") (pintype "unspecified"))
      (node (ref "U2") (pin "43") (pinfunction "LX_43") (pintype "unspecified"))
    )
    (net (code "61") (name "Net-(U2-MICBIAS)") (class "Default")
      (node (ref "C12") (pin "2") (pinfunction "2_2") (pintype "unspecified"))
      (node (ref "U2") (pin "10") (pinfunction "MICBIAS_10") (pintype "unspecified"))
    )
    (net (code "62") (name "Net-(U2-VA18)") (class "Default")
      (node (ref "C14") (pin "2") (pinfunction "2_2") (pintype "unspecified"))
      (node (ref "U2") (pin "11") (pinfunction "VA18_11") (pintype "unspecified"))
    )
    (net (code "63") (name "Net-(U2-VDIGI)") (class "Default")
      (node (ref "C10") (pin "1") (pinfunction "1_1") (pintype "unspecified"))
      (node (ref "U2") (pin "41") (pinfunction "VDIGI_41") (pintype "unspecified"))
    )
    (net (code "64") (name "Net-(U4-VCC)") (class "Default")
      (node (ref "Q2") (pin "3") (pinfunction "3_3") (pintype "unspecified"))
      (node (ref "U4") (pin "8") (pinfunction "VCC_8") (pintype "unspecified"))
    )
    (net (code "65") (name "Net-(U6-EN)") (class "Default")
      (node (ref "C28") (pin "2") (pinfunction "2_2") (pintype "unspecified"))
      (node (ref "D4") (pin "1") (pinfunction "1_1") (pintype "unspecified"))
      (node (ref "D5") (pin "1") (pinfunction "1_1") (pintype "unspecified"))
      (node (ref "U6") (pin "1") (pinfunction "VIN_1") (pintype "unspecified"))
      (node (ref "U6") (pin "3") (pinfunction "EN_3") (pintype "unspecified"))
    )
    (net (code "66") (name "Net-(U8-KEY1)") (class "Default")
      (node (ref "C37") (pin "1") (pinfunction "1_1") (pintype "unspecified"))
      (node (ref "TP1") (pin "1") (pinfunction "1_1") (pintype "unspecified"))
      (node (ref "U8") (pin "2") (pinfunction "KEY1_2") (pintype "unspecified"))
    )
    (net (code "67") (name "Net-(U8-KEY2)") (class "Default")
      (node (ref "C36") (pin "1") (pinfunction "1_1") (pintype "unspecified"))
      (node (ref "TP2") (pin "1") (pinfunction "1_1") (pintype "unspecified"))
      (node (ref "U8") (pin "3") (pinfunction "KEY2_3") (pintype "unspecified"))
    )
    (net (code "68") (name "Net-(U8-KEY3)") (class "Default")
      (node (ref "C35") (pin "1") (pinfunction "1_1") (pintype "unspecified"))
      (node (ref "TP3") (pin "1") (pinfunction "1_1") (pintype "unspecified"))
      (node (ref "U8") (pin "4") (pinfunction "KEY3_4") (pintype "unspecified"))
    )
    (net (code "69") (name "Net-(U8-KEY4)") (class "Default")
      (node (ref "C34") (pin "1") (pinfunction "1_1") (pintype "unspecified"))
      (node (ref "TP4") (pin "1") (pinfunction "1_1") (pintype "unspecified"))
      (node (ref "U8") (pin "5") (pinfunction "KEY4_5") (pintype "unspecified"))
    )
    (net (code "70") (name "Net-(U9-BAT)") (class "Default")
      (node (ref "BAT1") (pin "1") (pintype "unspecified"))
      (node (ref "C40") (pin "2") (pinfunction "2_2") (pintype "unspecified"))
      (node (ref "D5") (pin "2") (pinfunction "2_2") (pintype "unspecified"))
      (node (ref "U9") (pin "3") (pinfunction "BAT_3") (pintype "unspecified"))
    )
    (net (code "71") (name "Net-(U9-CHRG#)") (class "Default")
      (node (ref "R8") (pin "2") (pinfunction "2_2") (pintype "unspecified"))
      (node (ref "U9") (pin "1") (pinfunction "CHRG#_1") (pintype "unspecified"))
    )
    (net (code "72") (name "Net-(U9-PROG)") (class "Default")
      (node (ref "R12") (pin "2") (pinfunction "2_2") (pintype "unspecified"))
      (node (ref "U9") (pin "6") (pinfunction "PROG_6") (pintype "unspecified"))
    )
    (net (code "73") (name "Net-(U9-STDBY#)") (class "Default")
      (node (ref "R11") (pin "2") (pinfunction "2_2") (pintype "unspecified"))
      (node (ref "U9") (pin "5") (pinfunction "STDBY#_5") (pintype "unspecified"))
    )
    (net (code "74") (name "Net-(U9-VCC)") (class "Default")
      (node (ref "C39") (pin "2") (pinfunction "2_2") (pintype "unspecified"))
      (node (ref "D2") (pin "A") (pinfunction "A_A") (pintype "unspecified"))
      (node (ref "D3") (pin "A") (pinfunction "A_A") (pintype "unspecified"))
      (node (ref "D4") (pin "2") (pinfunction "2_2") (pintype "unspecified"))
      (node (ref "U9") (pin "4") (pinfunction "VCC_4") (pintype "unspecified"))
      (node (ref "USB1") (pin "1") (pinfunction "VCC_1") (pintype "unspecified"))
    )
    (net (code "75") (name "VDD12") (class "Default")
      (node (ref "C15") (pin "1") (pinfunction "1_1") (pintype "unspecified"))
      (node (ref "C17") (pin "1") (pinfunction "1_1") (pintype "unspecified"))
      (node (ref "C19") (pin "2") (pinfunction "2_2") (pintype "unspecified"))
      (node (ref "C4") (pin "1") (pinfunction "1_1") (pintype "unspecified"))
      (node (ref "C7") (pin "2") (pinfunction "2_2") (pintype "unspecified"))
      (node (ref "L1") (pin "2") (pintype "unspecified"))
      (node (ref "T2") (pin "1") (pinfunction "TP_1") (pintype "unspecified"))
      (node (ref "U2") (pin "12") (pinfunction "VD12_TRX_12") (pintype "unspecified"))
      (node (ref "U2") (pin "14") (pinfunction "VD12_PA_14") (pintype "unspecified"))
      (node (ref "U2") (pin "15") (pinfunction "VD12_SYN_15") (pintype "unspecified"))
      (node (ref "U2") (pin "42") (pinfunction "VDDCORE_42") (pintype "unspecified"))
    )
    (net (code "76") (name "unconnected-(B1-Pad3)") (class "Default")
      (node (ref "B1") (pin "3") (pinfunction "3_3") (pintype "unspecified+no_connect"))
    )
    (net (code "77") (name "unconnected-(B1-Pad4)") (class "Default")
      (node (ref "B1") (pin "4") (pinfunction "4_4") (pintype "unspecified+no_connect"))
    )
    (net (code "78") (name "unconnected-(BTB1-DB08-Pad4)") (class "Default")
      (node (ref "BTB1") (pin "4") (pinfunction "DB08_4") (pintype "unspecified+no_connect"))
    )
    (net (code "79") (name "unconnected-(K1-Pad2)") (class "Default")
      (node (ref "K1") (pin "2") (pintype "unspecified+no_connect"))
    )
    (net (code "80") (name "unconnected-(K1-Pad3)") (class "Default")
      (node (ref "K1") (pin "3") (pintype "unspecified+no_connect"))
    )
    (net (code "81") (name "unconnected-(K2-Pad1)") (class "Default")
      (node (ref "K2") (pin "1") (pintype "unspecified+no_connect"))
    )
    (net (code "82") (name "unconnected-(K2-Pad4)") (class "Default")
      (node (ref "K2") (pin "4") (pintype "unspecified+no_connect"))
    )
    (net (code "83") (name "unconnected-(U1-NC-Pad2)") (class "Default")
      (node (ref "U1") (pin "2") (pinfunction "NC_2") (pintype "unspecified+no_connect"))
    )
    (net (code "84") (name "unconnected-(U5-CSB-Pad10)") (class "Default")
      (node (ref "U5") (pin "10") (pinfunction "CSB_10") (pintype "unspecified+no_connect"))
    )
    (net (code "85") (name "unconnected-(U5-INT2-Pad6)") (class "Default")
      (node (ref "U5") (pin "6") (pinfunction "INT2_6") (pintype "unspecified+no_connect"))
    )
    (net (code "86") (name "unconnected-(U6-NC-Pad4)") (class "Default")
      (node (ref "U6") (pin "4") (pinfunction "NC_4") (pintype "unspecified+no_connect"))
    )
    (net (code "87") (name "unconnected-(U7-CTS#-Pad5)") (class "Default")
      (node (ref "U7") (pin "5") (pinfunction "CTS#_5") (pintype "unspecified+no_connect"))
    )
    (net (code "88") (name "unconnected-(U7-RTS#-Pad4)") (class "Default")
      (node (ref "U7") (pin "4") (pinfunction "RTS#_4") (pintype "unspecified+no_connect"))
    )
    (net (code "89") (name "unconnected-(U7-TNOW-Pad6)") (class "Default")
      (node (ref "U7") (pin "6") (pinfunction "TNOW_6") (pintype "unspecified+no_connect"))
    )
    (net (code "90") (name "unconnected-(USB1-ID-Pad4)") (class "Default")
      (node (ref "USB1") (pin "4") (pinfunction "ID_4") (pintype "unspecified+no_connect"))
    )
  )
)
